# v1_2.net
KiCad netlist of a schematic drawn in EAGLE
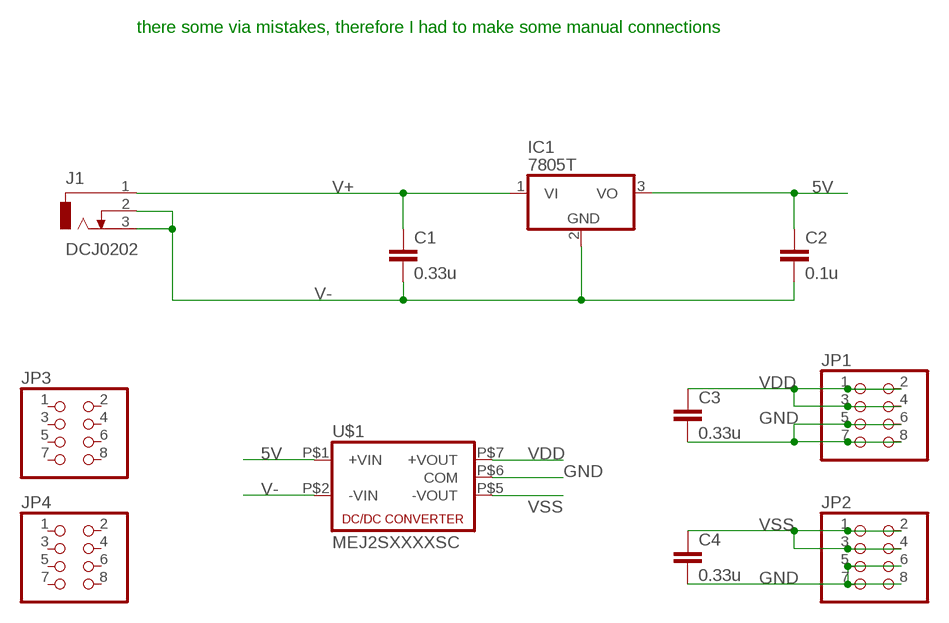
[diagram p0: schematic, sheet 1]

(export (version "E")
  (design (tool "Eeschema 10.0.6"))
  (components
    (comp (ref "C1")
      (value "0.33u")
      (footprint "eagle-import:C050-045X075")
      (libsource (lib "eagle-import") (part "C-EU050-045X075"))
    )
    (comp (ref "C2")
      (value "0.1u")
      (footprint "eagle-import:C050-045X075")
      (libsource (lib "eagle-import") (part "C-EU050-045X075"))
    )
    (comp (ref "C3")
      (value "0.33u")
      (footprint "eagle-import:C050-045X075")
      (libsource (lib "eagle-import") (part "C-EU050-045X075"))
    )
    (comp (ref "C4")
      (value "0.33u")
      (footprint "eagle-import:C050-045X075")
      (libsource (lib "eagle-import") (part "C-EU050-045X075"))
    )
    (comp (ref "IC1")
      (value "7805T")
      (footprint "eagle-import:TO220H")
      (libsource (lib "eagle-import") (part "78T05"))
    )
    (comp (ref "J1")
      (value "DCJ0202")
      (footprint "eagle-import:DCJ0202")
      (libsource (lib "eagle-import") (part "DCJ0202"))
    )
    (comp (ref "JP1")
      (value "PINHD-2X4")
      (footprint "eagle-import:2X04")
      (libsource (lib "eagle-import") (part "PINHD-2X4"))
    )
    (comp (ref "JP2")
      (value "PINHD-2X4")
      (footprint "eagle-import:2X04")
      (libsource (lib "eagle-import") (part "PINHD-2X4"))
    )
    (comp (ref "JP3")
      (value "PINHD-2X4")
      (footprint "eagle-import:2X04")
      (libsource (lib "eagle-import") (part "PINHD-2X4"))
    )
    (comp (ref "JP4")
      (value "PINHD-2X4")
      (footprint "eagle-import:2X04")
      (libsource (lib "eagle-import") (part "PINHD-2X4"))
    )
    (comp (ref "U$1")
      (value "MEJ2SXXXXSC")
      (footprint "eagle-import:NMA")
      (libsource (lib "eagle-import") (part "MEJ2SXXXXSC"))
    )
  )
  (nets
    (net (code "1") (name "/5V") (class "Default")
      (node (ref "C2") (pin "1") (pinfunction "1_1") (pintype "passive"))
      (node (ref "IC1") (pin "3") (pinfunction "VO_3") (pintype "passive"))
      (node (ref "U$1") (pin "P$1") (pinfunction "+VIN_P$1") (pintype "passive"))
    )
    (net (code "2") (name "/GND") (class "Default")
      (node (ref "C3") (pin "2") (pinfunction "2_2") (pintype "passive"))
      (node (ref "C4") (pin "2") (pinfunction "2_2") (pintype "passive"))
      (node (ref "JP1") (pin "5") (pinfunction "5_5") (pintype "passive"))
      (node (ref "JP1") (pin "6") (pinfunction "6_6") (pintype "passive"))
      (node (ref "JP1") (pin "7") (pinfunction "7_7") (pintype "passive"))
      (node (ref "JP1") (pin "8") (pinfunction "8_8") (pintype "passive"))
      (node (ref "JP2") (pin "5") (pinfunction "5_5") (pintype "passive"))
      (node (ref "JP2") (pin "6") (pinfunction "6_6") (pintype "passive"))
      (node (ref "JP2") (pin "7") (pinfunction "7_7") (pintype "passive"))
      (node (ref "JP2") (pin "8") (pinfunction "8_8") (pintype "passive"))
      (node (ref "U$1") (pin "P$6") (pinfunction "COM_P$6") (pintype "passive"))
    )
    (net (code "3") (name "/V+") (class "Default")
      (node (ref "C1") (pin "1") (pinfunction "1_1") (pintype "passive"))
      (node (ref "IC1") (pin "1") (pinfunction "VI_1") (pintype "input"))
      (node (ref "J1") (pin "1") (pinfunction "1_1") (pintype "passive"))
    )
    (net (code "4") (name "/V-") (class "Default")
      (node (ref "C1") (pin "2") (pinfunction "2_2") (pintype "passive"))
      (node (ref "C2") (pin "2") (pinfunction "2_2") (pintype "passive"))
      (node (ref "IC1") (pin "2") (pinfunction "GND_2") (pintype "passive"))
      (node (ref "J1") (pin "2") (pinfunction "2_2") (pintype "passive"))
      (node (ref "J1") (pin "3") (pinfunction "3_3") (pintype "passive"))
      (node (ref "U$1") (pin "P$2") (pinfunction "-VIN_P$2") (pintype "passive"))
    )
    (net (code "5") (name "/VDD") (class "Default")
      (node (ref "C3") (pin "1") (pinfunction "1_1") (pintype "passive"))
      (node (ref "JP1") (pin "1") (pinfunction "1_1") (pintype "passive"))
      (node (ref "JP1") (pin "2") (pinfunction "2_2") (pintype "passive"))
      (node (ref "JP1") (pin "3") (pinfunction "3_3") (pintype "passive"))
      (node (ref "JP1") (pin "4") (pinfunction "4_4") (pintype "passive"))
      (node (ref "U$1") (pin "P$7") (pinfunction "+VOUT_P$7") (pintype "passive"))
    )
    (net (code "6") (name "/VSS") (class "Default")
      (node (ref "C4") (pin "1") (pinfunction "1_1") (pintype "passive"))
      (node (ref "JP2") (pin "1") (pinfunction "1_1") (pintype "passive"))
      (node (ref "JP2") (pin "2") (pinfunction "2_2") (pintype "passive"))
      (node (ref "JP2") (pin "3") (pinfunction "3_3") (pintype "passive"))
      (node (ref "JP2") (pin "4") (pinfunction "4_4") (pintype "passive"))
      (node (ref "U$1") (pin "P$5") (pinfunction "-VOUT_P$5") (pintype "passive"))
    )
    (net (code "7") (name "unconnected-(JP3-Pad1)") (class "Default")
      (node (ref "JP3") (pin "1") (pinfunction "1_1") (pintype "passive"))
    )
    (net (code "8") (name "unconnected-(JP3-Pad2)") (class "Default")
      (node (ref "JP3") (pin "2") (pinfunction "2_2") (pintype "passive"))
    )
    (net (code "9") (name "unconnected-(JP3-Pad3)") (class "Default")
      (node (ref "JP3") (pin "3") (pinfunction "3_3") (pintype "passive"))
    )
    (net (code "10") (name "unconnected-(JP3-Pad4)") (class "Default")
      (node (ref "JP3") (pin "4") (pinfunction "4_4") (pintype "passive"))
    )
    (net (code "11") (name "unconnected-(JP3-Pad5)") (class "Default")
      (node (ref "JP3") (pin "5") (pinfunction "5_5") (pintype "passive"))
    )
    (net (code "12") (name "unconnected-(JP3-Pad6)") (class "Default")
      (node (ref "JP3") (pin "6") (pinfunction "6_6") (pintype "passive"))
    )
    (net (code "13") (name "unconnected-(JP3-Pad7)") (class "Default")
      (node (ref "JP3") (pin "7") (pinfunction "7_7") (pintype "passive"))
    )
    (net (code "14") (name "unconnected-(JP3-Pad8)") (class "Default")
      (node (ref "JP3") (pin "8") (pinfunction "8_8") (pintype "passive"))
    )
    (net (code "15") (name "unconnected-(JP4-Pad1)") (class "Default")
      (node (ref "JP4") (pin "1") (pinfunction "1_1") (pintype "passive"))
    )
    (net (code "16") (name "unconnected-(JP4-Pad2)") (class "Default")
      (node (ref "JP4") (pin "2") (pinfunction "2_2") (pintype "passive"))
    )
    (net (code "17") (name "unconnected-(JP4-Pad3)") (class "Default")
      (node (ref "JP4") (pin "3") (pinfunction "3_3") (pintype "passive"))
    )
    (net (code "18") (name "unconnected-(JP4-Pad4)") (class "Default")
      (node (ref "JP4") (pin "4") (pinfunction "4_4") (pintype "passive"))
    )
    (net (code "19") (name "unconnected-(JP4-Pad5)") (class "Default")
      (node (ref "JP4") (pin "5") (pinfunction "5_5") (pintype "passive"))
    )
    (net (code "20") (name "unconnected-(JP4-Pad6)") (class "Default")
      (node (ref "JP4") (pin "6") (pinfunction "6_6") (pintype "passive"))
    )
    (net (code "21") (name "unconnected-(JP4-Pad7)") (class "Default")
      (node (ref "JP4") (pin "7") (pinfunction "7_7") (pintype "passive"))
    )
    (net (code "22") (name "unconnected-(JP4-Pad8)") (class "Default")
      (node (ref "JP4") (pin "8") (pinfunction "8_8") (pintype "passive"))
    )
  )
)
